# Open_Reactor_Control_System_-_Analogue_I.net
KiCad netlist of a schematic drawn in Altium Designer
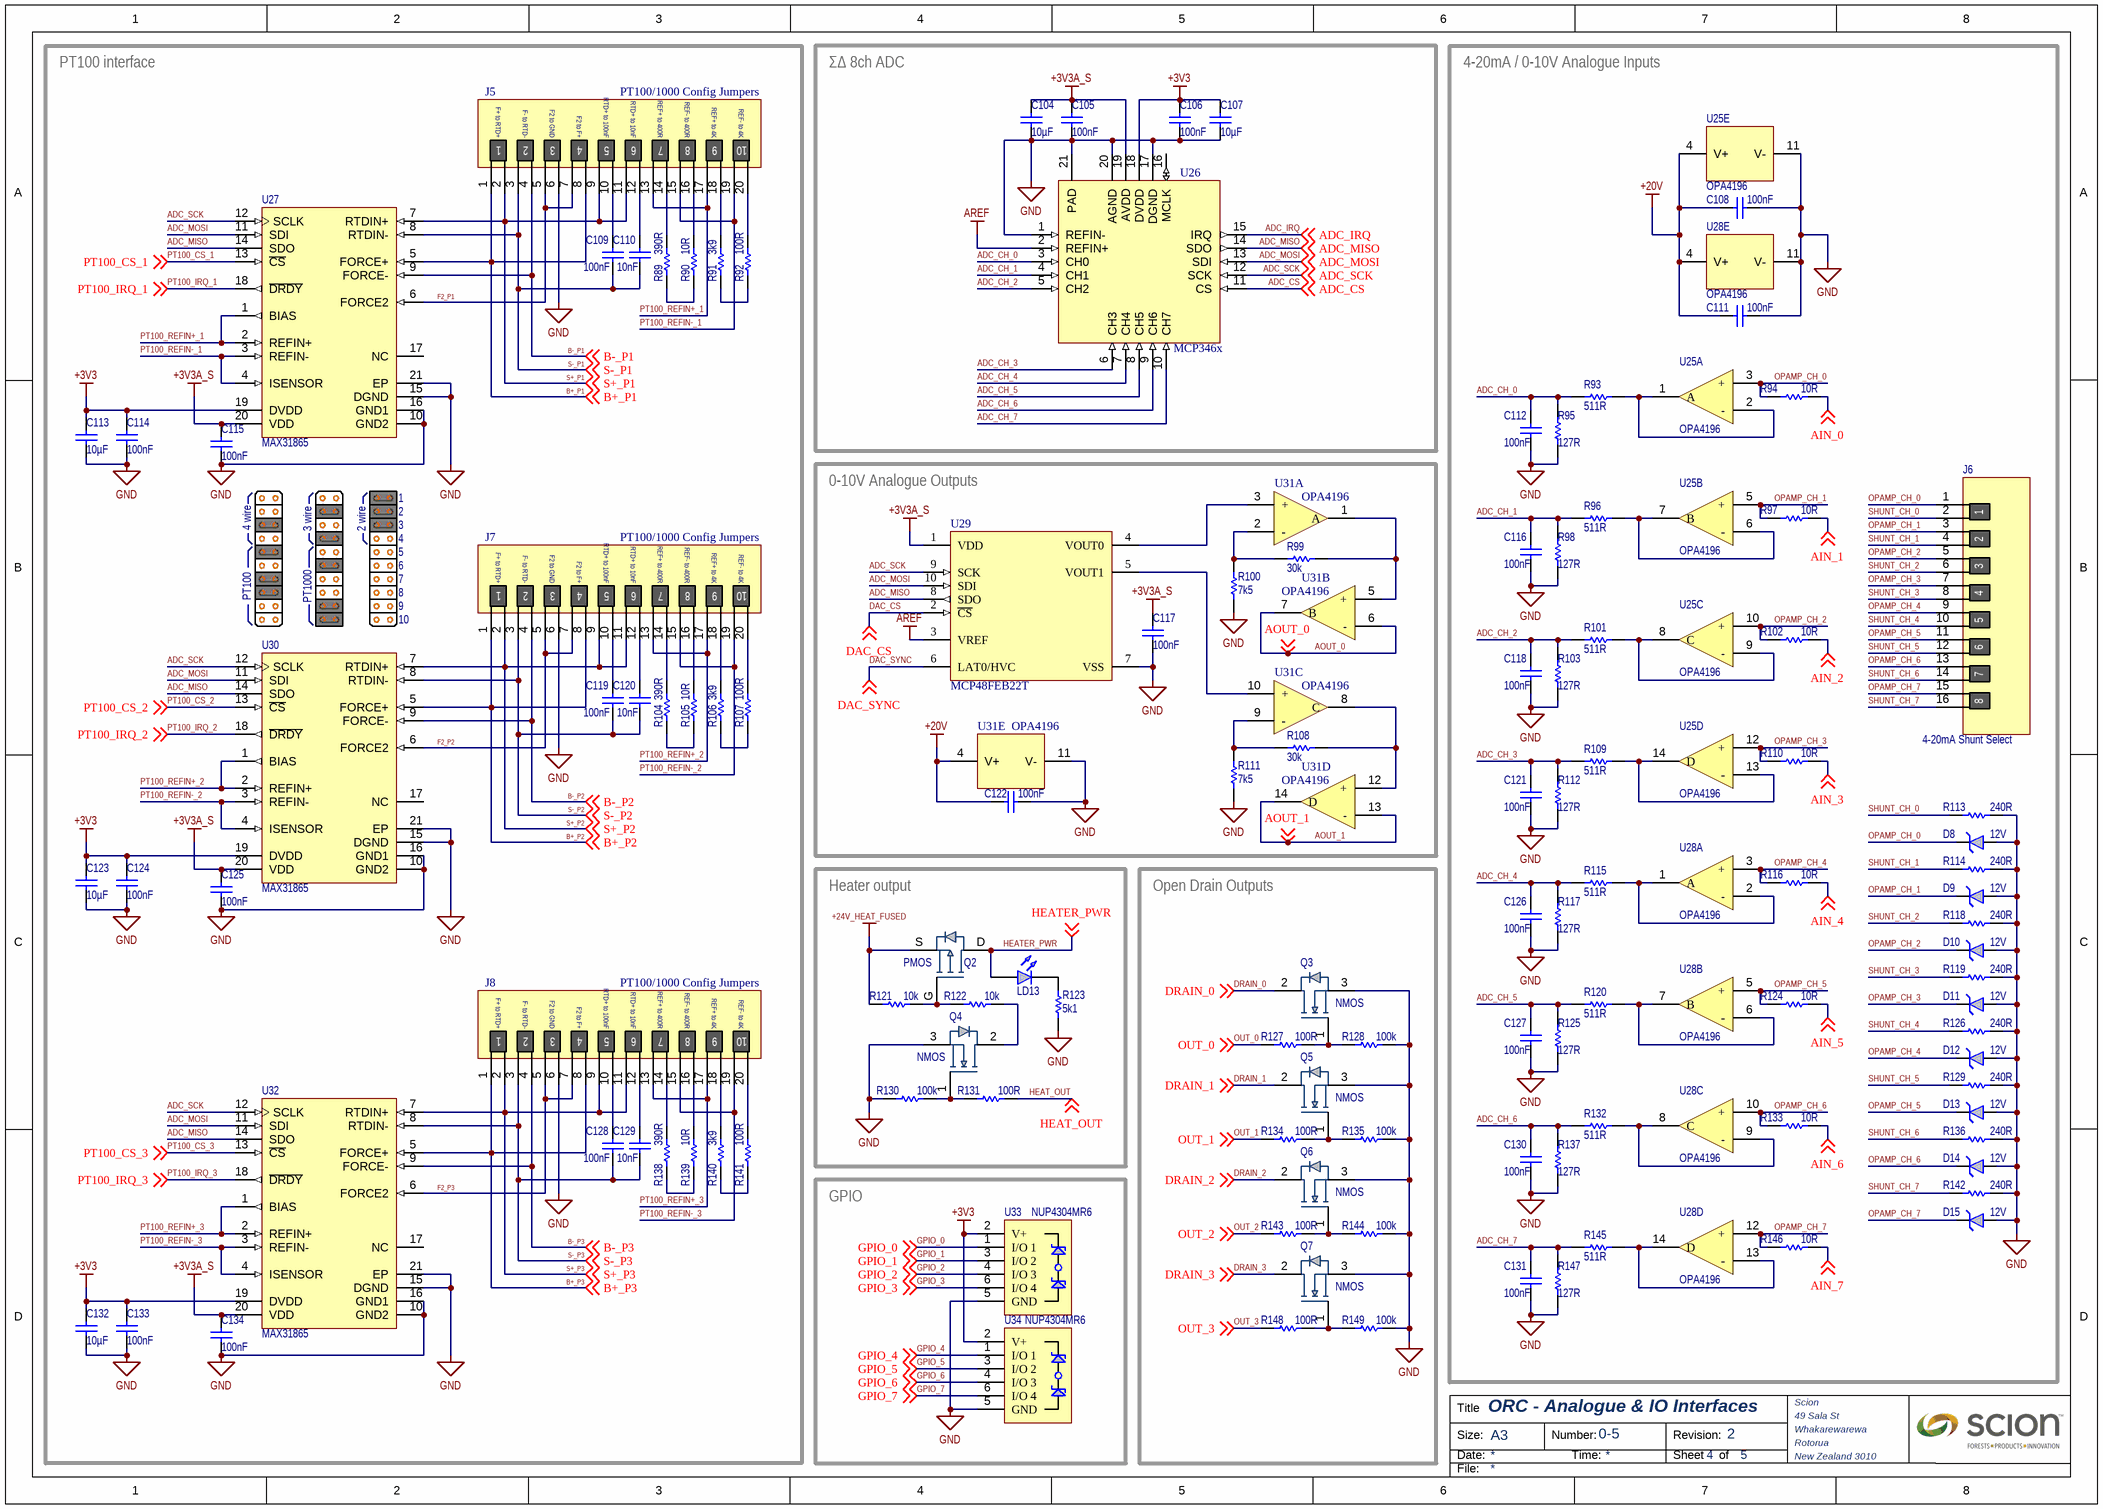
[diagram p0: Open Reactor Control System - Analogue & IO Interfaces.SchDoc]

(export (version "E")
  (design (tool "Eeschema 10.0.6"))
  (components
    (comp (ref "C104")
      (value "10µF")
      (footprint "0603_CAP")
      (description "SMD Capacitor")
      (fields (field (name "Comment") "Capacitor"))
      (libsource (lib "Scion Research") (part "CMP-019-00005-2"))
    )
    (comp (ref "C105")
      (value "100nF")
      (footprint "0603_CAP")
      (description "SMD Capacitor")
      (fields (field (name "Comment") "Capacitor"))
      (libsource (lib "Scion Research") (part "CMP-019-00005-2"))
    )
    (comp (ref "C106")
      (value "100nF")
      (footprint "0603_CAP")
      (description "SMD Capacitor")
      (fields (field (name "Comment") "Capacitor"))
      (libsource (lib "Scion Research") (part "CMP-019-00005-2"))
    )
    (comp (ref "C107")
      (value "10µF")
      (footprint "0603_CAP")
      (description "SMD Capacitor")
      (fields (field (name "Comment") "Capacitor"))
      (libsource (lib "Scion Research") (part "CMP-019-00005-2"))
    )
    (comp (ref "C108")
      (value "100nF")
      (footprint "0603_CAP")
      (description "SMD Capacitor")
      (fields (field (name "Comment") "Capacitor"))
      (libsource (lib "Scion Research") (part "CMP-019-00005-2"))
    )
    (comp (ref "C109")
      (value "100nF")
      (footprint "0603_CAP")
      (description "SMD Capacitor")
      (fields (field (name "Comment") "Capacitor"))
      (libsource (lib "Scion Research") (part "CMP-019-00005-2"))
    )
    (comp (ref "C110")
      (value "10nF")
      (footprint "0603_CAP")
      (description "SMD Capacitor")
      (fields (field (name "Comment") "Capacitor"))
      (libsource (lib "Scion Research") (part "CMP-019-00005-2"))
    )
    (comp (ref "C111")
      (value "100nF")
      (footprint "0603_CAP")
      (description "SMD Capacitor")
      (fields (field (name "Comment") "Capacitor"))
      (libsource (lib "Scion Research") (part "CMP-019-00005-2"))
    )
    (comp (ref "C112")
      (value "100nF")
      (footprint "0603_CAP")
      (description "SMD Capacitor")
      (fields (field (name "Comment") "Capacitor"))
      (libsource (lib "Scion Research") (part "CMP-019-00005-2"))
    )
    (comp (ref "C113")
      (value "10µF")
      (footprint "0603_CAP")
      (description "SMD Capacitor")
      (fields (field (name "Comment") "Capacitor"))
      (libsource (lib "Scion Research") (part "CMP-019-00005-2"))
    )
    (comp (ref "C114")
      (value "100nF")
      (footprint "0603_CAP")
      (description "SMD Capacitor")
      (fields (field (name "Comment") "Capacitor"))
      (libsource (lib "Scion Research") (part "CMP-019-00005-2"))
    )
    (comp (ref "C115")
      (value "100nF")
      (footprint "0603_CAP")
      (description "SMD Capacitor")
      (fields (field (name "Comment") "Capacitor"))
      (libsource (lib "Scion Research") (part "CMP-019-00005-2"))
    )
    (comp (ref "C116")
      (value "100nF")
      (footprint "0603_CAP")
      (description "SMD Capacitor")
      (fields (field (name "Comment") "Capacitor"))
      (libsource (lib "Scion Research") (part "CMP-019-00005-2"))
    )
    (comp (ref "C117")
      (value "100nF")
      (footprint "0603_CAP")
      (description "SMD Capacitor")
      (fields (field (name "Comment") "Capacitor"))
      (libsource (lib "Scion Research") (part "CMP-019-00005-2"))
    )
    (comp (ref "C118")
      (value "100nF")
      (footprint "0603_CAP")
      (description "SMD Capacitor")
      (fields (field (name "Comment") "Capacitor"))
      (libsource (lib "Scion Research") (part "CMP-019-00005-2"))
    )
    (comp (ref "C119")
      (value "100nF")
      (footprint "0603_CAP")
      (description "SMD Capacitor")
      (fields (field (name "Comment") "Capacitor"))
      (libsource (lib "Scion Research") (part "CMP-019-00005-2"))
    )
    (comp (ref "C120")
      (value "10nF")
      (footprint "0603_CAP")
      (description "SMD Capacitor")
      (fields (field (name "Comment") "Capacitor"))
      (libsource (lib "Scion Research") (part "CMP-019-00005-2"))
    )
    (comp (ref "C121")
      (value "100nF")
      (footprint "0603_CAP")
      (description "SMD Capacitor")
      (fields (field (name "Comment") "Capacitor"))
      (libsource (lib "Scion Research") (part "CMP-019-00005-2"))
    )
    (comp (ref "C122")
      (value "100nF")
      (footprint "0603_CAP")
      (description "SMD Capacitor")
      (fields (field (name "Comment") "Capacitor"))
      (libsource (lib "Scion Research") (part "CMP-019-00005-2"))
    )
    (comp (ref "C123")
      (value "10µF")
      (footprint "0603_CAP")
      (description "SMD Capacitor")
      (fields (field (name "Comment") "Capacitor"))
      (libsource (lib "Scion Research") (part "CMP-019-00005-2"))
    )
    (comp (ref "C124")
      (value "100nF")
      (footprint "0603_CAP")
      (description "SMD Capacitor")
      (fields (field (name "Comment") "Capacitor"))
      (libsource (lib "Scion Research") (part "CMP-019-00005-2"))
    )
    (comp (ref "C125")
      (value "100nF")
      (footprint "0603_CAP")
      (description "SMD Capacitor")
      (fields (field (name "Comment") "Capacitor"))
      (libsource (lib "Scion Research") (part "CMP-019-00005-2"))
    )
    (comp (ref "C126")
      (value "100nF")
      (footprint "0603_CAP")
      (description "SMD Capacitor")
      (fields (field (name "Comment") "Capacitor"))
      (libsource (lib "Scion Research") (part "CMP-019-00005-2"))
    )
    (comp (ref "C127")
      (value "100nF")
      (footprint "0603_CAP")
      (description "SMD Capacitor")
      (fields (field (name "Comment") "Capacitor"))
      (libsource (lib "Scion Research") (part "CMP-019-00005-2"))
    )
    (comp (ref "C128")
      (value "100nF")
      (footprint "0603_CAP")
      (description "SMD Capacitor")
      (fields (field (name "Comment") "Capacitor"))
      (libsource (lib "Scion Research") (part "CMP-019-00005-2"))
    )
    (comp (ref "C129")
      (value "10nF")
      (footprint "0603_CAP")
      (description "SMD Capacitor")
      (fields (field (name "Comment") "Capacitor"))
      (libsource (lib "Scion Research") (part "CMP-019-00005-2"))
    )
    (comp (ref "C130")
      (value "100nF")
      (footprint "0603_CAP")
      (description "SMD Capacitor")
      (fields (field (name "Comment") "Capacitor"))
      (libsource (lib "Scion Research") (part "CMP-019-00005-2"))
    )
    (comp (ref "C131")
      (value "100nF")
      (footprint "0603_CAP")
      (description "SMD Capacitor")
      (fields (field (name "Comment") "Capacitor"))
      (libsource (lib "Scion Research") (part "CMP-019-00005-2"))
    )
    (comp (ref "C132")
      (value "10µF")
      (footprint "0603_CAP")
      (description "SMD Capacitor")
      (fields (field (name "Comment") "Capacitor"))
      (libsource (lib "Scion Research") (part "CMP-019-00005-2"))
    )
    (comp (ref "C133")
      (value "100nF")
      (footprint "0603_CAP")
      (description "SMD Capacitor")
      (fields (field (name "Comment") "Capacitor"))
      (libsource (lib "Scion Research") (part "CMP-019-00005-2"))
    )
    (comp (ref "C134")
      (value "100nF")
      (footprint "0603_CAP")
      (description "SMD Capacitor")
      (fields (field (name "Comment") "Capacitor"))
      (libsource (lib "Scion Research") (part "CMP-019-00005-2"))
    )
    (comp (ref "D8")
      (value "Transil")
      (footprint "SMBJ")
      (description "Transient Voltage Suppressor")
      (fields (field (name "RATED VOLTAGE") "12V"))
      (libsource (lib "Scion Research") (part "CMP-004-0042-1"))
    )
    (comp (ref "D9")
      (value "Transil")
      (footprint "SMBJ")
      (description "Transient Voltage Suppressor")
      (fields (field (name "RATED VOLTAGE") "12V"))
      (libsource (lib "Scion Research") (part "CMP-004-0042-1"))
    )
    (comp (ref "D10")
      (value "Transil")
      (footprint "SMBJ")
      (description "Transient Voltage Suppressor")
      (fields (field (name "RATED VOLTAGE") "12V"))
      (libsource (lib "Scion Research") (part "CMP-004-0042-1"))
    )
    (comp (ref "D11")
      (value "Transil")
      (footprint "SMBJ")
      (description "Transient Voltage Suppressor")
      (fields (field (name "RATED VOLTAGE") "12V"))
      (libsource (lib "Scion Research") (part "CMP-004-0042-1"))
    )
    (comp (ref "D12")
      (value "Transil")
      (footprint "SMBJ")
      (description "Transient Voltage Suppressor")
      (fields (field (name "RATED VOLTAGE") "12V"))
      (libsource (lib "Scion Research") (part "CMP-004-0042-1"))
    )
    (comp (ref "D13")
      (value "Transil")
      (footprint "SMBJ")
      (description "Transient Voltage Suppressor")
      (fields (field (name "RATED VOLTAGE") "12V"))
      (libsource (lib "Scion Research") (part "CMP-004-0042-1"))
    )
    (comp (ref "D14")
      (value "Transil")
      (footprint "SMBJ")
      (description "Transient Voltage Suppressor")
      (fields (field (name "RATED VOLTAGE") "12V"))
      (libsource (lib "Scion Research") (part "CMP-004-0042-1"))
    )
    (comp (ref "D15")
      (value "Transil")
      (footprint "SMBJ")
      (description "Transient Voltage Suppressor")
      (fields (field (name "RATED VOLTAGE") "12V"))
      (libsource (lib "Scion Research") (part "CMP-004-0042-1"))
    )
    (comp (ref "J5")
      (value "PT100/1000 Config Jumpers")
      (footprint "20P 1.27mm SMD DIP male header")
      (description "20 pin connector")
      (libsource (lib "Scion Research") (part "20_Pin-Symbol-1"))
    )
    (comp (ref "J6")
      (value "4-20mA Shunt Select")
      (footprint "16P 1.27mm SMD DIP male header")
      (description "16 Pin Connector")
      (libsource (lib "Scion Research") (part "16_Pin_SIL"))
    )
    (comp (ref "J7")
      (value "PT100/1000 Config Jumpers")
      (footprint "20P 1.27mm SMD DIP male header")
      (description "20 pin connector")
      (libsource (lib "Scion Research") (part "20_Pin-Symbol-1"))
    )
    (comp (ref "J8")
      (value "PT100/1000 Config Jumpers")
      (footprint "20P 1.27mm SMD DIP male header")
      (description "20 pin connector")
      (libsource (lib "Scion Research") (part "20_Pin-Symbol-1"))
    )
    (comp (ref "LD13")
      (value "LED")
      (footprint "0805")
      (description "SMD LED")
      (libsource (lib "Scion Research") (part "CMP-004-00032-1"))
    )
    (comp (ref "Q2")
      (value "PMOS")
      (footprint "PowerDI 5060-8")
      (description "P Channel MOSFET")
      (libsource (lib "Scion Research") (part "CMP-004-0035-2"))
    )
    (comp (ref "Q3")
      (value "NMOS")
      (footprint "SOT-23")
      (description "N Channel MOSFET")
      (libsource (lib "Scion Research") (part "CMP-004-0025-1"))
    )
    (comp (ref "Q4")
      (value "NMOS")
      (footprint "SOT-23")
      (description "N Channel MOSFET")
      (libsource (lib "Scion Research") (part "CMP-004-0025-1"))
    )
    (comp (ref "Q5")
      (value "NMOS")
      (footprint "SOT-23")
      (description "N Channel MOSFET")
      (libsource (lib "Scion Research") (part "CMP-004-0025-1"))
    )
    (comp (ref "Q6")
      (value "NMOS")
      (footprint "SOT-23")
      (description "N Channel MOSFET")
      (libsource (lib "Scion Research") (part "CMP-004-0025-1"))
    )
    (comp (ref "Q7")
      (value "NMOS")
      (footprint "SOT-23")
      (description "N Channel MOSFET")
      (libsource (lib "Scion Research") (part "CMP-004-0025-1"))
    )
    (comp (ref "R89")
      (value "390R")
      (footprint "0603_RES")
      (description "SMD Resistor")
      (fields (field (name "Comment") "Resistor"))
      (libsource (lib "Scion Research") (part "Resistor SMD"))
    )
    (comp (ref "R90")
      (value "10R")
      (footprint "0603_RES")
      (description "SMD Resistor")
      (fields (field (name "Comment") "Resistor"))
      (libsource (lib "Scion Research") (part "Resistor SMD"))
    )
    (comp (ref "R91")
      (value "3k9")
      (footprint "0603_RES")
      (description "SMD Resistor")
      (fields (field (name "Comment") "Resistor"))
      (libsource (lib "Scion Research") (part "Resistor SMD"))
    )
    (comp (ref "R92")
      (value "100R")
      (footprint "0603_RES")
      (description "SMD Resistor")
      (fields (field (name "Comment") "Resistor"))
      (libsource (lib "Scion Research") (part "Resistor SMD"))
    )
    (comp (ref "R93")
      (value "511R")
      (footprint "0603_RES")
      (description "SMD Resistor")
      (fields (field (name "Comment") "Resistor"))
      (libsource (lib "Scion Research") (part "Resistor SMD"))
    )
    (comp (ref "R94")
      (value "10R")
      (footprint "0603_RES")
      (description "SMD Resistor")
      (fields (field (name "Comment") "Resistor"))
      (libsource (lib "Scion Research") (part "Resistor SMD"))
    )
    (comp (ref "R95")
      (value "127R")
      (footprint "0603_RES")
      (description "SMD Resistor")
      (fields (field (name "Comment") "Resistor"))
      (libsource (lib "Scion Research") (part "Resistor SMD"))
    )
    (comp (ref "R96")
      (value "511R")
      (footprint "0603_RES")
      (description "SMD Resistor")
      (fields (field (name "Comment") "Resistor"))
      (libsource (lib "Scion Research") (part "Resistor SMD"))
    )
    (comp (ref "R97")
      (value "10R")
      (footprint "0603_RES")
      (description "SMD Resistor")
      (fields (field (name "Comment") "Resistor"))
      (libsource (lib "Scion Research") (part "Resistor SMD"))
    )
    (comp (ref "R98")
      (value "127R")
      (footprint "0603_RES")
      (description "SMD Resistor")
      (fields (field (name "Comment") "Resistor"))
      (libsource (lib "Scion Research") (part "Resistor SMD"))
    )
    (comp (ref "R99")
      (value "30k")
      (footprint "0603_RES")
      (description "SMD Resistor")
      (fields (field (name "Comment") "Resistor"))
      (libsource (lib "Scion Research") (part "Resistor SMD"))
    )
    (comp (ref "R100")
      (value "7k5")
      (footprint "0603_RES")
      (description "SMD Resistor")
      (fields (field (name "Comment") "Resistor"))
      (libsource (lib "Scion Research") (part "Resistor SMD"))
    )
    (comp (ref "R101")
      (value "511R")
      (footprint "0603_RES")
      (description "SMD Resistor")
      (fields (field (name "Comment") "Resistor"))
      (libsource (lib "Scion Research") (part "Resistor SMD"))
    )
    (comp (ref "R102")
      (value "10R")
      (footprint "0603_RES")
      (description "SMD Resistor")
      (fields (field (name "Comment") "Resistor"))
      (libsource (lib "Scion Research") (part "Resistor SMD"))
    )
    (comp (ref "R103")
      (value "127R")
      (footprint "0603_RES")
      (description "SMD Resistor")
      (fields (field (name "Comment") "Resistor"))
      (libsource (lib "Scion Research") (part "Resistor SMD"))
    )
    (comp (ref "R104")
      (value "390R")
      (footprint "0603_RES")
      (description "SMD Resistor")
      (fields (field (name "Comment") "Resistor"))
      (libsource (lib "Scion Research") (part "Resistor SMD"))
    )
    (comp (ref "R105")
      (value "10R")
      (footprint "0603_RES")
      (description "SMD Resistor")
      (fields (field (name "Comment") "Resistor"))
      (libsource (lib "Scion Research") (part "Resistor SMD"))
    )
    (comp (ref "R106")
      (value "3k9")
      (footprint "0603_RES")
      (description "SMD Resistor")
      (fields (field (name "Comment") "Resistor"))
      (libsource (lib "Scion Research") (part "Resistor SMD"))
    )
    (comp (ref "R107")
      (value "100R")
      (footprint "0603_RES")
      (description "SMD Resistor")
      (fields (field (name "Comment") "Resistor"))
      (libsource (lib "Scion Research") (part "Resistor SMD"))
    )
    (comp (ref "R108")
      (value "30k")
      (footprint "0603_RES")
      (description "SMD Resistor")
      (fields (field (name "Comment") "Resistor"))
      (libsource (lib "Scion Research") (part "Resistor SMD"))
    )
    (comp (ref "R109")
      (value "511R")
      (footprint "0603_RES")
      (description "SMD Resistor")
      (fields (field (name "Comment") "Resistor"))
      (libsource (lib "Scion Research") (part "Resistor SMD"))
    )
    (comp (ref "R110")
      (value "10R")
      (footprint "0603_RES")
      (description "SMD Resistor")
      (fields (field (name "Comment") "Resistor"))
      (libsource (lib "Scion Research") (part "Resistor SMD"))
    )
    (comp (ref "R111")
      (value "7k5")
      (footprint "0603_RES")
      (description "SMD Resistor")
      (fields (field (name "Comment") "Resistor"))
      (libsource (lib "Scion Research") (part "Resistor SMD"))
    )
    (comp (ref "R112")
      (value "127R")
      (footprint "0603_RES")
      (description "SMD Resistor")
      (fields (field (name "Comment") "Resistor"))
      (libsource (lib "Scion Research") (part "Resistor SMD"))
    )
    (comp (ref "R113")
      (value "Resistor")
      (footprint "1206_RES")
      (description "SMD Resistor")
      (fields (field (name "ALTIUM_VALUE") "240R"))
      (libsource (lib "Scion Research") (part "CMP-009-00177-2"))
    )
    (comp (ref "R114")
      (value "Resistor")
      (footprint "1206_RES")
      (description "SMD Resistor")
      (fields (field (name "ALTIUM_VALUE") "240R"))
      (libsource (lib "Scion Research") (part "CMP-009-00177-2"))
    )
    (comp (ref "R115")
      (value "511R")
      (footprint "0603_RES")
      (description "SMD Resistor")
      (fields (field (name "Comment") "Resistor"))
      (libsource (lib "Scion Research") (part "Resistor SMD"))
    )
    (comp (ref "R116")
      (value "10R")
      (footprint "0603_RES")
      (description "SMD Resistor")
      (fields (field (name "Comment") "Resistor"))
      (libsource (lib "Scion Research") (part "Resistor SMD"))
    )
    (comp (ref "R117")
      (value "127R")
      (footprint "0603_RES")
      (description "SMD Resistor")
      (fields (field (name "Comment") "Resistor"))
      (libsource (lib "Scion Research") (part "Resistor SMD"))
    )
    (comp (ref "R118")
      (value "Resistor")
      (footprint "1206_RES")
      (description "SMD Resistor")
      (fields (field (name "ALTIUM_VALUE") "240R"))
      (libsource (lib "Scion Research") (part "CMP-009-00177-2"))
    )
    (comp (ref "R119")
      (value "Resistor")
      (footprint "1206_RES")
      (description "SMD Resistor")
      (fields (field (name "ALTIUM_VALUE") "240R"))
      (libsource (lib "Scion Research") (part "CMP-009-00177-2"))
    )
    (comp (ref "R120")
      (value "511R")
      (footprint "0603_RES")
      (description "SMD Resistor")
      (fields (field (name "Comment") "Resistor"))
      (libsource (lib "Scion Research") (part "Resistor SMD"))
    )
    (comp (ref "R121")
      (value "10k")
      (footprint "0603_RES")
      (description "SMD Resistor")
      (fields (field (name "Comment") "Resistor"))
      (libsource (lib "Scion Research") (part "Resistor SMD"))
    )
    (comp (ref "R122")
      (value "10k")
      (footprint "0603_RES")
      (description "SMD Resistor")
      (fields (field (name "Comment") "Resistor"))
      (libsource (lib "Scion Research") (part "Resistor SMD"))
    )
    (comp (ref "R123")
      (value "Resistor")
      (footprint "0603_RES")
      (description "SMD Resistor")
      (fields (field (name "ALTIUM_VALUE") "5k1"))
      (libsource (lib "Scion Research") (part "CMP-009-00177-2"))
    )
    (comp (ref "R124")
      (value "10R")
      (footprint "0603_RES")
      (description "SMD Resistor")
      (fields (field (name "Comment") "Resistor"))
      (libsource (lib "Scion Research") (part "Resistor SMD"))
    )
    (comp (ref "R125")
      (value "127R")
      (footprint "0603_RES")
      (description "SMD Resistor")
      (fields (field (name "Comment") "Resistor"))
      (libsource (lib "Scion Research") (part "Resistor SMD"))
    )
    (comp (ref "R126")
      (value "Resistor")
      (footprint "1206_RES")
      (description "SMD Resistor")
      (fields (field (name "ALTIUM_VALUE") "240R"))
      (libsource (lib "Scion Research") (part "CMP-009-00177-2"))
    )
    (comp (ref "R127")
      (value "100R")
      (footprint "0603_RES")
      (description "SMD Resistor")
      (fields (field (name "Comment") "Resistor"))
      (libsource (lib "Scion Research") (part "Resistor SMD"))
    )
    (comp (ref "R128")
      (value "100k")
      (footprint "0603_RES")
      (description "SMD Resistor")
      (fields (field (name "Comment") "Resistor"))
      (libsource (lib "Scion Research") (part "Resistor SMD"))
    )
    (comp (ref "R129")
      (value "Resistor")
      (footprint "1206_RES")
      (description "SMD Resistor")
      (fields (field (name "ALTIUM_VALUE") "240R"))
      (libsource (lib "Scion Research") (part "CMP-009-00177-2"))
    )
    (comp (ref "R130")
      (value "100k")
      (footprint "0603_RES")
      (description "SMD Resistor")
      (fields (field (name "Comment") "Resistor"))
      (libsource (lib "Scion Research") (part "Resistor SMD"))
    )
    (comp (ref "R131")
      (value "100R")
      (footprint "0603_RES")
      (description "SMD Resistor")
      (fields (field (name "Comment") "Resistor"))
      (libsource (lib "Scion Research") (part "Resistor SMD"))
    )
    (comp (ref "R132")
      (value "511R")
      (footprint "0603_RES")
      (description "SMD Resistor")
      (fields (field (name "Comment") "Resistor"))
      (libsource (lib "Scion Research") (part "Resistor SMD"))
    )
    (comp (ref "R133")
      (value "10R")
      (footprint "0603_RES")
      (description "SMD Resistor")
      (fields (field (name "Comment") "Resistor"))
      (libsource (lib "Scion Research") (part "Resistor SMD"))
    )
    (comp (ref "R134")
      (value "100R")
      (footprint "0603_RES")
      (description "SMD Resistor")
      (fields (field (name "Comment") "Resistor"))
      (libsource (lib "Scion Research") (part "Resistor SMD"))
    )
    (comp (ref "R135")
      (value "100k")
      (footprint "0603_RES")
      (description "SMD Resistor")
      (fields (field (name "Comment") "Resistor"))
      (libsource (lib "Scion Research") (part "Resistor SMD"))
    )
    (comp (ref "R136")
      (value "Resistor")
      (footprint "1206_RES")
      (description "SMD Resistor")
      (fields (field (name "ALTIUM_VALUE") "240R"))
      (libsource (lib "Scion Research") (part "CMP-009-00177-2"))
    )
    (comp (ref "R137")
      (value "127R")
      (footprint "0603_RES")
      (description "SMD Resistor")
      (fields (field (name "Comment") "Resistor"))
      (libsource (lib "Scion Research") (part "Resistor SMD"))
    )
    (comp (ref "R138")
      (value "390R")
      (footprint "0603_RES")
      (description "SMD Resistor")
      (fields (field (name "Comment") "Resistor"))
      (libsource (lib "Scion Research") (part "Resistor SMD"))
    )
    (comp (ref "R139")
      (value "10R")
      (footprint "0603_RES")
      (description "SMD Resistor")
      (fields (field (name "Comment") "Resistor"))
      (libsource (lib "Scion Research") (part "Resistor SMD"))
    )
    (comp (ref "R140")
      (value "3k9")
      (footprint "0603_RES")
      (description "SMD Resistor")
      (fields (field (name "Comment") "Resistor"))
      (libsource (lib "Scion Research") (part "Resistor SMD"))
    )
    (comp (ref "R141")
      (value "100R")
      (footprint "0603_RES")
      (description "SMD Resistor")
      (fields (field (name "Comment") "Resistor"))
      (libsource (lib "Scion Research") (part "Resistor SMD"))
    )
    (comp (ref "R142")
      (value "Resistor")
      (footprint "1206_RES")
      (description "SMD Resistor")
      (fields (field (name "ALTIUM_VALUE") "240R"))
      (libsource (lib "Scion Research") (part "CMP-009-00177-2"))
    )
    (comp (ref "R143")
      (value "100R")
      (footprint "0603_RES")
      (description "SMD Resistor")
      (fields (field (name "Comment") "Resistor"))
      (libsource (lib "Scion Research") (part "Resistor SMD"))
    )
    (comp (ref "R144")
      (value "100k")
      (footprint "0603_RES")
      (description "SMD Resistor")
      (fields (field (name "Comment") "Resistor"))
      (libsource (lib "Scion Research") (part "Resistor SMD"))
    )
    (comp (ref "R145")
      (value "511R")
      (footprint "0603_RES")
      (description "SMD Resistor")
      (fields (field (name "Comment") "Resistor"))
      (libsource (lib "Scion Research") (part "Resistor SMD"))
    )
    (comp (ref "R146")
      (value "10R")
      (footprint "0603_RES")
      (description "SMD Resistor")
      (fields (field (name "Comment") "Resistor"))
      (libsource (lib "Scion Research") (part "Resistor SMD"))
    )
    (comp (ref "R147")
      (value "127R")
      (footprint "0603_RES")
      (description "SMD Resistor")
      (fields (field (name "Comment") "Resistor"))
      (libsource (lib "Scion Research") (part "Resistor SMD"))
    )
    (comp (ref "R148")
      (value "100R")
      (footprint "0603_RES")
      (description "SMD Resistor")
      (fields (field (name "Comment") "Resistor"))
      (libsource (lib "Scion Research") (part "Resistor SMD"))
    )
    (comp (ref "R149")
      (value "100k")
      (footprint "0603_RES")
      (description "SMD Resistor")
      (fields (field (name "Comment") "Resistor"))
      (libsource (lib "Scion Research") (part "Resistor SMD"))
    )
    (comp (ref "U25")
      (value "OPA4196")
      (footprint "SOIC_14")
      (description "Quad 36V OpAmp")
      (libsource (lib "") (part "CMP-004-0029-1_1"))
    )
    (comp (ref "U26")
      (value "MCP346x")
      (footprint "20P_TSSOP")
      (description "MCP3461/2/4 S? ADC")
      (libsource (lib "Scion Research") (part "MCP3464"))
    )
    (comp (ref "U27")
      (value "MAX31865")
      (footprint "MAXM-T2055+5_L")
      (description "IC RTD TO DIGITAL CONVERT 20TQFN")
      (libsource (lib "Scion Research") (part "CMP-00054-1"))
    )
    (comp (ref "U28")
      (value "OPA4196")
      (footprint "SOIC_14")
      (description "Quad 36V OpAmp")
      (libsource (lib "Scion Research") (part "CMP-004-0029-1"))
    )
    (comp (ref "U29")
      (value "MCP48FEB22T")
      (footprint "FP-C04-021-UN-IPC_C")
      (description "D/A Converter, 1 Func, Serial Input Loading, 7.8us Settling Time, PDSO10")
      (libsource (lib "Scion Research") (part "MCP48FEB22"))
    )
    (comp (ref "U30")
      (value "MAX31865")
      (footprint "MAXM-T2055+5_L")
      (description "IC RTD TO DIGITAL CONVERT 20TQFN")
      (libsource (lib "Scion Research") (part "CMP-00054-1"))
    )
    (comp (ref "U31")
      (value "OPA4196")
      (footprint "SOIC_14")
      (description "Quad 36V OpAmp")
      (libsource (lib "") (part "CMP-004-0029-1_1"))
    )
    (comp (ref "U32")
      (value "MAX31865")
      (footprint "MAXM-T2055+5_L")
      (description "IC RTD TO DIGITAL CONVERT 20TQFN")
      (libsource (lib "Scion Research") (part "CMP-00054-1"))
    )
    (comp (ref "U33")
      (value "NUP4304MR6")
      (footprint "TSOP-6")
      (description "ESD Protection Doide Array")
      (libsource (lib "Scion Research") (part "CMP-004-0028-1"))
    )
    (comp (ref "U34")
      (value "NUP4304MR6")
      (footprint "TSOP-6")
      (description "ESD Protection Doide Array")
      (libsource (lib "Scion Research") (part "CMP-004-0028-1"))
    )
  )
  (nets
    (net (code "1") (name "+3V3") (class "Default")
      (node (ref "C106") (pin "1") (pinfunction "1_1") (pintype "passive"))
      (node (ref "C107") (pin "1") (pinfunction "1_1") (pintype "passive"))
      (node (ref "C113") (pin "1") (pinfunction "1_1") (pintype "passive"))
      (node (ref "C114") (pin "1") (pinfunction "1_1") (pintype "passive"))
      (node (ref "C123") (pin "1") (pinfunction "1_1") (pintype "passive"))
      (node (ref "C124") (pin "1") (pinfunction "1_1") (pintype "passive"))
      (node (ref "C132") (pin "1") (pinfunction "1_1") (pintype "passive"))
      (node (ref "C133") (pin "1") (pinfunction "1_1") (pintype "passive"))
      (node (ref "U26") (pin "18") (pinfunction "DVDD_18") (pintype "power_in"))
      (node (ref "U27") (pin "19") (pinfunction "DVDD_19") (pintype "power_in"))
      (node (ref "U30") (pin "19") (pinfunction "DVDD_19") (pintype "power_in"))
      (node (ref "U32") (pin "19") (pinfunction "DVDD_19") (pintype "power_in"))
      (node (ref "U33") (pin "2") (pinfunction "V+_2") (pintype "power_in"))
      (node (ref "U34") (pin "2") (pinfunction "V+_2") (pintype "power_in"))
    )
    (net (code "2") (name "+3V3A_S") (class "Default")
      (node (ref "C104") (pin "1") (pinfunction "1_1") (pintype "passive"))
      (node (ref "C105") (pin "1") (pinfunction "1_1") (pintype "passive"))
      (node (ref "C115") (pin "1") (pinfunction "1_1") (pintype "passive"))
      (node (ref "C117") (pin "1") (pinfunction "1_1") (pintype "passive"))
      (node (ref "C125") (pin "1") (pinfunction "1_1") (pintype "passive"))
      (node (ref "C134") (pin "1") (pinfunction "1_1") (pintype "passive"))
      (node (ref "U26") (pin "19") (pinfunction "AVDD_19") (pintype "power_in"))
      (node (ref "U27") (pin "20") (pinfunction "VDD_20") (pintype "power_in"))
      (node (ref "U29") (pin "1") (pinfunction "VDD_1") (pintype "power_in"))
      (node (ref "U30") (pin "20") (pinfunction "VDD_20") (pintype "power_in"))
      (node (ref "U32") (pin "20") (pinfunction "VDD_20") (pintype "power_in"))
    )
    (net (code "3") (name "+20V") (class "Default")
      (node (ref "C108") (pin "1") (pinfunction "1_1") (pintype "passive"))
      (node (ref "C111") (pin "1") (pinfunction "1_1") (pintype "passive"))
      (node (ref "C122") (pin "2") (pinfunction "2_2") (pintype "passive"))
      (node (ref "U25") (pin "4") (pinfunction "V+_4") (pintype "passive"))
      (node (ref "U28") (pin "4") (pinfunction "V+_4") (pintype "passive"))
      (node (ref "U31") (pin "4") (pinfunction "V+_4") (pintype "passive"))
    )
    (net (code "4") (name "+24V_HEAT_FUSED") (class "Default")
      (node (ref "Q2") (pin "S") (pinfunction "S_S") (pintype "passive"))
      (node (ref "R121") (pin "2") (pinfunction "2_2") (pintype "passive"))
    )
    (net (code "5") (name "/ADC_CH_0") (class "Default")
      (node (ref "C112") (pin "1") (pinfunction "1_1") (pintype "passive"))
      (node (ref "R93") (pin "2") (pinfunction "2_2") (pintype "passive"))
      (node (ref "R95") (pin "2") (pinfunction "2_2") (pintype "passive"))
      (node (ref "U26") (pin "3") (pinfunction "CH0_3") (pintype "input"))
    )
    (net (code "6") (name "/ADC_CH_1") (class "Default")
      (node (ref "C116") (pin "1") (pinfunction "1_1") (pintype "passive"))
      (node (ref "R96") (pin "2") (pinfunction "2_2") (pintype "passive"))
      (node (ref "R98") (pin "2") (pinfunction "2_2") (pintype "passive"))
      (node (ref "U26") (pin "4") (pinfunction "CH1_4") (pintype "input"))
    )
    (net (code "7") (name "/ADC_CH_2") (class "Default")
      (node (ref "C118") (pin "1") (pinfunction "1_1") (pintype "passive"))
      (node (ref "R101") (pin "2") (pinfunction "2_2") (pintype "passive"))
      (node (ref "R103") (pin "2") (pinfunction "2_2") (pintype "passive"))
      (node (ref "U26") (pin "5") (pinfunction "CH2_5") (pintype "input"))
    )
    (net (code "8") (name "/ADC_CH_3") (class "Default")
      (node (ref "C121") (pin "1") (pinfunction "1_1") (pintype "passive"))
      (node (ref "R109") (pin "2") (pinfunction "2_2") (pintype "passive"))
      (node (ref "R112") (pin "2") (pinfunction "2_2") (pintype "passive"))
      (node (ref "U26") (pin "6") (pinfunction "CH3_6") (pintype "input"))
    )
    (net (code "9") (name "/ADC_CH_4") (class "Default")
      (node (ref "C126") (pin "1") (pinfunction "1_1") (pintype "passive"))
      (node (ref "R115") (pin "2") (pinfunction "2_2") (pintype "passive"))
      (node (ref "R117") (pin "2") (pinfunction "2_2") (pintype "passive"))
      (node (ref "U26") (pin "7") (pinfunction "CH4_7") (pintype "input"))
    )
    (net (code "10") (name "/ADC_CH_5") (class "Default")
      (node (ref "C127") (pin "1") (pinfunction "1_1") (pintype "passive"))
      (node (ref "R120") (pin "2") (pinfunction "2_2") (pintype "passive"))
      (node (ref "R125") (pin "2") (pinfunction "2_2") (pintype "passive"))
      (node (ref "U26") (pin "8") (pinfunction "CH5_8") (pintype "input"))
    )
    (net (code "11") (name "/ADC_CH_6") (class "Default")
      (node (ref "C130") (pin "1") (pinfunction "1_1") (pintype "passive"))
      (node (ref "R132") (pin "2") (pinfunction "2_2") (pintype "passive"))
      (node (ref "R137") (pin "2") (pinfunction "2_2") (pintype "passive"))
      (node (ref "U26") (pin "9") (pinfunction "CH6_9") (pintype "input"))
    )
    (net (code "12") (name "/ADC_CH_7") (class "Default")
      (node (ref "C131") (pin "1") (pinfunction "1_1") (pintype "passive"))
      (node (ref "R145") (pin "2") (pinfunction "2_2") (pintype "passive"))
      (node (ref "R147") (pin "2") (pinfunction "2_2") (pintype "passive"))
      (node (ref "U26") (pin "10") (pinfunction "CH7_10") (pintype "input"))
    )
    (net (code "13") (name "/F2_P1") (class "Default")
      (node (ref "J5") (pin "5") (pinfunction "5_5") (pintype "passive"))
      (node (ref "J5") (pin "7") (pinfunction "7_7") (pintype "passive"))
      (node (ref "U27") (pin "6") (pinfunction "FORCE2_6") (pintype "input"))
    )
    (net (code "14") (name "/F2_P2") (class "Default")
      (node (ref "J7") (pin "5") (pinfunction "5_5") (pintype "passive"))
      (node (ref "J7") (pin "7") (pinfunction "7_7") (pintype "passive"))
      (node (ref "U30") (pin "6") (pinfunction "FORCE2_6") (pintype "input"))
    )
    (net (code "15") (name "/F2_P3") (class "Default")
      (node (ref "J8") (pin "5") (pinfunction "5_5") (pintype "passive"))
      (node (ref "J8") (pin "7") (pinfunction "7_7") (pintype "passive"))
      (node (ref "U32") (pin "6") (pinfunction "FORCE2_6") (pintype "input"))
    )
    (net (code "16") (name "/OPAMP_CH_0") (class "Default")
      (node (ref "D8") (pin "2") (pinfunction "K_2") (pintype "passive"))
      (node (ref "J6") (pin "1") (pinfunction "1_1") (pintype "passive"))
      (node (ref "R94") (pin "2") (pinfunction "2_2") (pintype "passive"))
      (node (ref "U25") (pin "3") (pinfunction "+_3") (pintype "passive"))
    )
    (net (code "17") (name "/OPAMP_CH_1") (class "Default")
      (node (ref "D9") (pin "2") (pinfunction "K_2") (pintype "passive"))
      (node (ref "J6") (pin "3") (pinfunction "3_3") (pintype "passive"))
      (node (ref "R97") (pin "2") (pinfunction "2_2") (pintype "passive"))
      (node (ref "U25") (pin "5") (pinfunction "+_5") (pintype "passive"))
    )
    (net (code "18") (name "/OPAMP_CH_2") (class "Default")
      (node (ref "D10") (pin "2") (pinfunction "K_2") (pintype "passive"))
      (node (ref "J6") (pin "5") (pinfunction "5_5") (pintype "passive"))
      (node (ref "R102") (pin "2") (pinfunction "2_2") (pintype "passive"))
      (node (ref "U25") (pin "10") (pinfunction "+_10") (pintype "passive"))
    )
    (net (code "19") (name "/OPAMP_CH_3") (class "Default")
      (node (ref "D11") (pin "2") (pinfunction "K_2") (pintype "passive"))
      (node (ref "J6") (pin "7") (pinfunction "7_7") (pintype "passive"))
      (node (ref "R110") (pin "2") (pinfunction "2_2") (pintype "passive"))
      (node (ref "U25") (pin "12") (pinfunction "+_12") (pintype "passive"))
    )
    (net (code "20") (name "/OPAMP_CH_4") (class "Default")
      (node (ref "D12") (pin "2") (pinfunction "K_2") (pintype "passive"))
      (node (ref "J6") (pin "9") (pinfunction "9_9") (pintype "passive"))
      (node (ref "R116") (pin "2") (pinfunction "2_2") (pintype "passive"))
      (node (ref "U28") (pin "3") (pinfunction "+_3") (pintype "passive"))
    )
    (net (code "21") (name "/OPAMP_CH_5") (class "Default")
      (node (ref "D13") (pin "2") (pinfunction "K_2") (pintype "passive"))
      (node (ref "J6") (pin "11") (pinfunction "11_11") (pintype "passive"))
      (node (ref "R124") (pin "2") (pinfunction "2_2") (pintype "passive"))
      (node (ref "U28") (pin "5") (pinfunction "+_5") (pintype "passive"))
    )
    (net (code "22") (name "/OPAMP_CH_6") (class "Default")
      (node (ref "D14") (pin "2") (pinfunction "K_2") (pintype "passive"))
      (node (ref "J6") (pin "13") (pinfunction "13_13") (pintype "passive"))
      (node (ref "R133") (pin "2") (pinfunction "2_2") (pintype "passive"))
      (node (ref "U28") (pin "10") (pinfunction "+_10") (pintype "passive"))
    )
    (net (code "23") (name "/OPAMP_CH_7") (class "Default")
      (node (ref "D15") (pin "2") (pinfunction "K_2") (pintype "passive"))
      (node (ref "J6") (pin "15") (pinfunction "15_15") (pintype "passive"))
      (node (ref "R146") (pin "2") (pinfunction "2_2") (pintype "passive"))
      (node (ref "U28") (pin "12") (pinfunction "+_12") (pintype "passive"))
    )
    (net (code "24") (name "/PT100_REFIN+_1") (class "Default")
      (node (ref "J5") (pin "13") (pinfunction "13_13") (pintype "passive"))
      (node (ref "J5") (pin "17") (pinfunction "17_17") (pintype "passive"))
      (node (ref "U27") (pin "1") (pinfunction "BIAS_1") (pintype "output"))
      (node (ref "U27") (pin "2") (pinfunction "REFIN+_2") (pintype "input"))
    )
    (net (code "25") (name "/PT100_REFIN+_2") (class "Default")
      (node (ref "J7") (pin "13") (pinfunction "13_13") (pintype "passive"))
      (node (ref "J7") (pin "17") (pinfunction "17_17") (pintype "passive"))
      (node (ref "U30") (pin "1") (pinfunction "BIAS_1") (pintype "output"))
      (node (ref "U30") (pin "2") (pinfunction "REFIN+_2") (pintype "input"))
    )
    (net (code "26") (name "/PT100_REFIN+_3") (class "Default")
      (node (ref "J8") (pin "13") (pinfunction "13_13") (pintype "passive"))
      (node (ref "J8") (pin "17") (pinfunction "17_17") (pintype "passive"))
      (node (ref "U32") (pin "1") (pinfunction "BIAS_1") (pintype "output"))
      (node (ref "U32") (pin "2") (pinfunction "REFIN+_2") (pintype "input"))
    )
    (net (code "27") (name "/PT100_REFIN-_1") (class "Default")
      (node (ref "J5") (pin "15") (pinfunction "15_15") (pintype "passive"))
      (node (ref "J5") (pin "19") (pinfunction "19_19") (pintype "passive"))
      (node (ref "U27") (pin "3") (pinfunction "REFIN-_3") (pintype "input"))
      (node (ref "U27") (pin "4") (pinfunction "ISENSOR_4") (pintype "input"))
    )
    (net (code "28") (name "/PT100_REFIN-_2") (class "Default")
      (node (ref "J7") (pin "15") (pinfunction "15_15") (pintype "passive"))
      (node (ref "J7") (pin "19") (pinfunction "19_19") (pintype "passive"))
      (node (ref "U30") (pin "3") (pinfunction "REFIN-_3") (pintype "input"))
      (node (ref "U30") (pin "4") (pinfunction "ISENSOR_4") (pintype "input"))
    )
    (net (code "29") (name "/PT100_REFIN-_3") (class "Default")
      (node (ref "J8") (pin "15") (pinfunction "15_15") (pintype "passive"))
      (node (ref "J8") (pin "19") (pinfunction "19_19") (pintype "passive"))
      (node (ref "U32") (pin "3") (pinfunction "REFIN-_3") (pintype "input"))
      (node (ref "U32") (pin "4") (pinfunction "ISENSOR_4") (pintype "input"))
    )
    (net (code "30") (name "/SHUNT_CH_0") (class "Default")
      (node (ref "J6") (pin "2") (pinfunction "2_2") (pintype "passive"))
      (node (ref "R113") (pin "2") (pinfunction "2_2") (pintype "passive"))
    )
    (net (code "31") (name "/SHUNT_CH_1") (class "Default")
      (node (ref "J6") (pin "4") (pinfunction "4_4") (pintype "passive"))
      (node (ref "R114") (pin "2") (pinfunction "2_2") (pintype "passive"))
    )
    (net (code "32") (name "/SHUNT_CH_2") (class "Default")
      (node (ref "J6") (pin "6") (pinfunction "6_6") (pintype "passive"))
      (node (ref "R118") (pin "2") (pinfunction "2_2") (pintype "passive"))
    )
    (net (code "33") (name "/SHUNT_CH_3") (class "Default")
      (node (ref "J6") (pin "8") (pinfunction "8_8") (pintype "passive"))
      (node (ref "R119") (pin "2") (pinfunction "2_2") (pintype "passive"))
    )
    (net (code "34") (name "/SHUNT_CH_4") (class "Default")
      (node (ref "J6") (pin "10") (pinfunction "10_10") (pintype "passive"))
      (node (ref "R126") (pin "2") (pinfunction "2_2") (pintype "passive"))
    )
    (net (code "35") (name "/SHUNT_CH_5") (class "Default")
      (node (ref "J6") (pin "12") (pinfunction "12_12") (pintype "passive"))
      (node (ref "R129") (pin "2") (pinfunction "2_2") (pintype "passive"))
    )
    (net (code "36") (name "/SHUNT_CH_6") (class "Default")
      (node (ref "J6") (pin "14") (pinfunction "14_14") (pintype "passive"))
      (node (ref "R136") (pin "2") (pinfunction "2_2") (pintype "passive"))
    )
    (net (code "37") (name "/SHUNT_CH_7") (class "Default")
      (node (ref "J6") (pin "16") (pinfunction "16_16") (pintype "passive"))
      (node (ref "R142") (pin "2") (pinfunction "2_2") (pintype "passive"))
    )
    (net (code "38") (name "ADC_CS") (class "Default")
      (node (ref "U26") (pin "11") (pinfunction "CS_11") (pintype "input"))
    )
    (net (code "39") (name "ADC_IRQ") (class "Default")
      (node (ref "U26") (pin "15") (pinfunction "IRQ_15") (pintype "output"))
    )
    (net (code "40") (name "ADC_MISO") (class "Default")
      (node (ref "U26") (pin "14") (pinfunction "SDO_14") (pintype "output"))
      (node (ref "U27") (pin "14") (pinfunction "SDO_14") (pintype "tri_state"))
      (node (ref "U29") (pin "8") (pinfunction "SDO_8") (pintype "output"))
      (node (ref "U30") (pin "14") (pinfunction "SDO_14") (pintype "tri_state"))
      (node (ref "U32") (pin "14") (pinfunction "SDO_14") (pintype "tri_state"))
    )
    (net (code "41") (name "ADC_MOSI") (class "Default")
      (node (ref "U26") (pin "13") (pinfunction "SDI_13") (pintype "input"))
      (node (ref "U27") (pin "11") (pinfunction "SDI_11") (pintype "input"))
      (node (ref "U29") (pin "10") (pinfunction "SDI_10") (pintype "input"))
      (node (ref "U30") (pin "11") (pinfunction "SDI_11") (pintype "input"))
      (node (ref "U32") (pin "11") (pinfunction "SDI_11") (pintype "input"))
    )
    (net (code "42") (name "ADC_SCK") (class "Default")
      (node (ref "U26") (pin "12") (pinfunction "SCK_12") (pintype "input"))
      (node (ref "U27") (pin "12") (pinfunction "SCLK_12") (pintype "input"))
      (node (ref "U29") (pin "9") (pinfunction "SCK_9") (pintype "input"))
      (node (ref "U30") (pin "12") (pinfunction "SCLK_12") (pintype "input"))
      (node (ref "U32") (pin "12") (pinfunction "SCLK_12") (pintype "input"))
    )
    (net (code "43") (name "AIN_0") (class "Default")
      (node (ref "R94") (pin "1") (pinfunction "1_1") (pintype "passive"))
    )
    (net (code "44") (name "AIN_1") (class "Default")
      (node (ref "R97") (pin "1") (pinfunction "1_1") (pintype "passive"))
    )
    (net (code "45") (name "AIN_2") (class "Default")
      (node (ref "R102") (pin "1") (pinfunction "1_1") (pintype "passive"))
    )
    (net (code "46") (name "AIN_3") (class "Default")
      (node (ref "R110") (pin "1") (pinfunction "1_1") (pintype "passive"))
    )
    (net (code "47") (name "AIN_4") (class "Default")
      (node (ref "R116") (pin "1") (pinfunction "1_1") (pintype "passive"))
    )
    (net (code "48") (name "AIN_5") (class "Default")
      (node (ref "R124") (pin "1") (pinfunction "1_1") (pintype "passive"))
    )
    (net (code "49") (name "AIN_6") (class "Default")
      (node (ref "R133") (pin "1") (pinfunction "1_1") (pintype "passive"))
    )
    (net (code "50") (name "AIN_7") (class "Default")
      (node (ref "R146") (pin "1") (pinfunction "1_1") (pintype "passive"))
    )
    (net (code "51") (name "AOUT_0") (class "Default")
      (node (ref "U31") (pin "6") (pinfunction "-_6") (pintype "passive"))
      (node (ref "U31") (pin "7") (pinfunction "B_7") (pintype "passive"))
    )
    (net (code "52") (name "AOUT_1") (class "Default")
      (node (ref "U31") (pin "13") (pinfunction "-_13") (pintype "passive"))
      (node (ref "U31") (pin "14") (pinfunction "D_14") (pintype "passive"))
    )
    (net (code "53") (name "AREF") (class "Default")
      (node (ref "U26") (pin "2") (pinfunction "REFIN+_2") (pintype "input"))
      (node (ref "U29") (pin "3") (pinfunction "VREF_3") (pintype "passive"))
    )
    (net (code "54") (name "B+_P1") (class "Default")
      (node (ref "J5") (pin "1") (pinfunction "1_1") (pintype "passive"))
      (node (ref "J5") (pin "8") (pinfunction "8_8") (pintype "passive"))
      (node (ref "U27") (pin "5") (pinfunction "FORCE+_5") (pintype "input"))
    )
    (net (code "55") (name "B+_P2") (class "Default")
      (node (ref "J7") (pin "1") (pinfunction "1_1") (pintype "passive"))
      (node (ref "J7") (pin "8") (pinfunction "8_8") (pintype "passive"))
      (node (ref "U30") (pin "5") (pinfunction "FORCE+_5") (pintype "input"))
    )
    (net (code "56") (name "B+_P3") (class "Default")
      (node (ref "J8") (pin "1") (pinfunction "1_1") (pintype "passive"))
      (node (ref "J8") (pin "8") (pinfunction "8_8") (pintype "passive"))
      (node (ref "U32") (pin "5") (pinfunction "FORCE+_5") (pintype "input"))
    )
    (net (code "57") (name "B-_P1") (class "Default")
      (node (ref "J5") (pin "4") (pinfunction "4_4") (pintype "passive"))
      (node (ref "U27") (pin "9") (pinfunction "FORCE-_9") (pintype "input"))
    )
    (net (code "58") (name "B-_P2") (class "Default")
      (node (ref "J7") (pin "4") (pinfunction "4_4") (pintype "passive"))
      (node (ref "U30") (pin "9") (pinfunction "FORCE-_9") (pintype "input"))
    )
    (net (code "59") (name "B-_P3") (class "Default")
      (node (ref "J8") (pin "4") (pinfunction "4_4") (pintype "passive"))
      (node (ref "U32") (pin "9") (pinfunction "FORCE-_9") (pintype "input"))
    )
    (net (code "60") (name "DAC_CS") (class "Default")
      (node (ref "U29") (pin "2") (pinfunction "~{CS}_2") (pintype "input"))
    )
    (net (code "61") (name "DAC_SYNC") (class "Default")
      (node (ref "U29") (pin "6") (pinfunction "LAT0/HVC_6") (pintype "passive"))
    )
    (net (code "62") (name "DRAIN_0") (class "Default")
      (node (ref "Q3") (pin "2") (pinfunction "D_2") (pintype "passive"))
    )
    (net (code "63") (name "DRAIN_1") (class "Default")
      (node (ref "Q5") (pin "2") (pinfunction "D_2") (pintype "passive"))
    )
    (net (code "64") (name "DRAIN_2") (class "Default")
      (node (ref "Q6") (pin "2") (pinfunction "D_2") (pintype "passive"))
    )
    (net (code "65") (name "DRAIN_3") (class "Default")
      (node (ref "Q7") (pin "2") (pinfunction "D_2") (pintype "passive"))
    )
    (net (code "66") (name "GND") (class "Default")
      (node (ref "C104") (pin "2") (pinfunction "2_2") (pintype "passive"))
      (node (ref "C105") (pin "2") (pinfunction "2_2") (pintype "passive"))
      (node (ref "C106") (pin "2") (pinfunction "2_2") (pintype "passive"))
      (node (ref "C107") (pin "2") (pinfunction "2_2") (pintype "passive"))
      (node (ref "C108") (pin "2") (pinfunction "2_2") (pintype "passive"))
      (node (ref "C111") (pin "2") (pinfunction "2_2") (pintype "passive"))
      (node (ref "C112") (pin "2") (pinfunction "2_2") (pintype "passive"))
      (node (ref "C113") (pin "2") (pinfunction "2_2") (pintype "passive"))
      (node (ref "C114") (pin "2") (pinfunction "2_2") (pintype "passive"))
      (node (ref "C115") (pin "2") (pinfunction "2_2") (pintype "passive"))
      (node (ref "C116") (pin "2") (pinfunction "2_2") (pintype "passive"))
      (node (ref "C117") (pin "2") (pinfunction "2_2") (pintype "passive"))
      (node (ref "C118") (pin "2") (pinfunction "2_2") (pintype "passive"))
      (node (ref "C121") (pin "2") (pinfunction "2_2") (pintype "passive"))
      (node (ref "C122") (pin "1") (pinfunction "1_1") (pintype "passive"))
      (node (ref "C123") (pin "2") (pinfunction "2_2") (pintype "passive"))
      (node (ref "C124") (pin "2") (pinfunction "2_2") (pintype "passive"))
      (node (ref "C125") (pin "2") (pinfunction "2_2") (pintype "passive"))
      (node (ref "C126") (pin "2") (pinfunction "2_2") (pintype "passive"))
      (node (ref "C127") (pin "2") (pinfunction "2_2") (pintype "passive"))
      (node (ref "C130") (pin "2") (pinfunction "2_2") (pintype "passive"))
      (node (ref "C131") (pin "2") (pinfunction "2_2") (pintype "passive"))
      (node (ref "C132") (pin "2") (pinfunction "2_2") (pintype "passive"))
      (node (ref "C133") (pin "2") (pinfunction "2_2") (pintype "passive"))
      (node (ref "C134") (pin "2") (pinfunction "2_2") (pintype "passive"))
      (node (ref "D10") (pin "1") (pinfunction "A_1") (pintype "passive"))
      (node (ref "D11") (pin "1") (pinfunction "A_1") (pintype "passive"))
      (node (ref "D12") (pin "1") (pinfunction "A_1") (pintype "passive"))
      (node (ref "D13") (pin "1") (pinfunction "A_1") (pintype "passive"))
      (node (ref "D14") (pin "1") (pinfunction "A_1") (pintype "passive"))
      (node (ref "D15") (pin "1") (pinfunction "A_1") (pintype "passive"))
      (node (ref "D8") (pin "1") (pinfunction "A_1") (pintype "passive"))
      (node (ref "D9") (pin "1") (pinfunction "A_1") (pintype "passive"))
      (node (ref "J5") (pin "6") (pinfunction "6_6") (pintype "passive"))
      (node (ref "J7") (pin "6") (pinfunction "6_6") (pintype "passive"))
      (node (ref "J8") (pin "6") (pinfunction "6_6") (pintype "passive"))
      (node (ref "Q3") (pin "3") (pinfunction "S_3") (pintype "passive"))
      (node (ref "Q4") (pin "3") (pinfunction "S_3") (pintype "passive"))
      (node (ref "Q5") (pin "3") (pinfunction "S_3") (pintype "passive"))
      (node (ref "Q6") (pin "3") (pinfunction "S_3") (pintype "passive"))
      (node (ref "Q7") (pin "3") (pinfunction "S_3") (pintype "passive"))
      (node (ref "R100") (pin "2") (pinfunction "2_2") (pintype "passive"))
      (node (ref "R103") (pin "1") (pinfunction "1_1") (pintype "passive"))
      (node (ref "R111") (pin "2") (pinfunction "2_2") (pintype "passive"))
      (node (ref "R112") (pin "1") (pinfunction "1_1") (pintype "passive"))
      (node (ref "R113") (pin "1") (pinfunction "1_1") (pintype "passive"))
      (node (ref "R114") (pin "1") (pinfunction "1_1") (pintype "passive"))
      (node (ref "R117") (pin "1") (pinfunction "1_1") (pintype "passive"))
      (node (ref "R118") (pin "1") (pinfunction "1_1") (pintype "passive"))
      (node (ref "R119") (pin "1") (pinfunction "1_1") (pintype "passive"))
      (node (ref "R123") (pin "1") (pinfunction "1_1") (pintype "passive"))
      (node (ref "R125") (pin "1") (pinfunction "1_1") (pintype "passive"))
      (node (ref "R126") (pin "1") (pinfunction "1_1") (pintype "passive"))
      (node (ref "R128") (pin "1") (pinfunction "1_1") (pintype "passive"))
      (node (ref "R129") (pin "1") (pinfunction "1_1") (pintype "passive"))
      (node (ref "R130") (pin "2") (pinfunction "2_2") (pintype "passive"))
      (node (ref "R135") (pin "1") (pinfunction "1_1") (pintype "passive"))
      (node (ref "R136") (pin "1") (pinfunction "1_1") (pintype "passive"))
      (node (ref "R137") (pin "1") (pinfunction "1_1") (pintype "passive"))
      (node (ref "R142") (pin "1") (pinfunction "1_1") (pintype "passive"))
      (node (ref "R144") (pin "1") (pinfunction "1_1") (pintype "passive"))
      (node (ref "R147") (pin "1") (pinfunction "1_1") (pintype "passive"))
      (node (ref "R149") (pin "1") (pinfunction "1_1") (pintype "passive"))
      (node (ref "R95") (pin "1") (pinfunction "1_1") (pintype "passive"))
      (node (ref "R98") (pin "1") (pinfunction "1_1") (pintype "passive"))
      (node (ref "U25") (pin "11") (pinfunction "V-_11") (pintype "passive"))
      (node (ref "U26") (pin "1") (pinfunction "REFIN-_1") (pintype "input"))
      (node (ref "U26") (pin "17") (pinfunction "DGND_17") (pintype "power_in"))
      (node (ref "U26") (pin "20") (pinfunction "AGND_20") (pintype "power_in"))
      (node (ref "U26") (pin "21") (pinfunction "PAD_21") (pintype "power_in"))
      (node (ref "U27") (pin "10") (pinfunction "GND2_10") (pintype "power_in"))
      (node (ref "U27") (pin "15") (pinfunction "DGND_15") (pintype "power_in"))
      (node (ref "U27") (pin "16") (pinfunction "GND1_16") (pintype "power_in"))
      (node (ref "U27") (pin "21") (pinfunction "EP_21") (pintype "power_in"))
      (node (ref "U28") (pin "11") (pinfunction "V-_11") (pintype "passive"))
      (node (ref "U29") (pin "7") (pinfunction "VSS_7") (pintype "power_in"))
      (node (ref "U30") (pin "10") (pinfunction "GND2_10") (pintype "power_in"))
      (node (ref "U30") (pin "15") (pinfunction "DGND_15") (pintype "power_in"))
      (node (ref "U30") (pin "16") (pinfunction "GND1_16") (pintype "power_in"))
      (node (ref "U30") (pin "21") (pinfunction "EP_21") (pintype "power_in"))
      (node (ref "U31") (pin "11") (pinfunction "V-_11") (pintype "passive"))
      (node (ref "U32") (pin "10") (pinfunction "GND2_10") (pintype "power_in"))
      (node (ref "U32") (pin "15") (pinfunction "DGND_15") (pintype "power_in"))
      (node (ref "U32") (pin "16") (pinfunction "GND1_16") (pintype "power_in"))
      (node (ref "U32") (pin "21") (pinfunction "EP_21") (pintype "power_in"))
      (node (ref "U33") (pin "5") (pinfunction "GND_5") (pintype "power_in"))
      (node (ref "U34") (pin "5") (pinfunction "GND_5") (pintype "power_in"))
    )
    (net (code "67") (name "GPIO_0") (class "Default")
      (node (ref "U33") (pin "1") (pinfunction "I/O_1_1") (pintype "power_in"))
    )
    (net (code "68") (name "GPIO_1") (class "Default")
      (node (ref "U33") (pin "3") (pinfunction "I/O_2_3") (pintype "power_in"))
    )
    (net (code "69") (name "GPIO_2") (class "Default")
      (node (ref "U33") (pin "4") (pinfunction "I/O_3_4") (pintype "power_in"))
    )
    (net (code "70") (name "GPIO_3") (class "Default")
      (node (ref "U33") (pin "6") (pinfunction "I/O_4_6") (pintype "power_in"))
    )
    (net (code "71") (name "GPIO_4") (class "Default")
      (node (ref "U34") (pin "1") (pinfunction "I/O_1_1") (pintype "power_in"))
    )
    (net (code "72") (name "GPIO_5") (class "Default")
      (node (ref "U34") (pin "3") (pinfunction "I/O_2_3") (pintype "power_in"))
    )
    (net (code "73") (name "GPIO_6") (class "Default")
      (node (ref "U34") (pin "4") (pinfunction "I/O_3_4") (pintype "power_in"))
    )
    (net (code "74") (name "GPIO_7") (class "Default")
      (node (ref "U34") (pin "6") (pinfunction "I/O_4_6") (pintype "power_in"))
    )
    (net (code "75") (name "HEATER_PWR") (class "Default")
      (node (ref "LD13") (pin "2") (pinfunction "A_2") (pintype "passive"))
      (node (ref "Q2") (pin "D") (pinfunction "D_D") (pintype "passive"))
    )
    (net (code "76") (name "HEAT_OUT") (class "Default")
      (node (ref "R131") (pin "1") (pinfunction "1_1") (pintype "passive"))
    )
    (net (code "77") (name "Net-(C109-Pad1)") (class "Default")
      (node (ref "C109") (pin "1") (pinfunction "1_1") (pintype "passive"))
      (node (ref "J5") (pin "10") (pinfunction "10_10") (pintype "passive"))
    )
    (net (code "78") (name "Net-(C110-Pad1)") (class "Default")
      (node (ref "C110") (pin "1") (pinfunction "1_1") (pintype "passive"))
      (node (ref "J5") (pin "12") (pinfunction "12_12") (pintype "passive"))
    )
    (net (code "79") (name "Net-(C119-Pad1)") (class "Default")
      (node (ref "C119") (pin "1") (pinfunction "1_1") (pintype "passive"))
      (node (ref "J7") (pin "10") (pinfunction "10_10") (pintype "passive"))
    )
    (net (code "80") (name "Net-(C120-Pad1)") (class "Default")
      (node (ref "C120") (pin "1") (pinfunction "1_1") (pintype "passive"))
      (node (ref "J7") (pin "12") (pinfunction "12_12") (pintype "passive"))
    )
    (net (code "81") (name "Net-(C128-Pad1)") (class "Default")
      (node (ref "C128") (pin "1") (pinfunction "1_1") (pintype "passive"))
      (node (ref "J8") (pin "10") (pinfunction "10_10") (pintype "passive"))
    )
    (net (code "82") (name "Net-(C129-Pad1)") (class "Default")
      (node (ref "C129") (pin "1") (pinfunction "1_1") (pintype "passive"))
      (node (ref "J8") (pin "12") (pinfunction "12_12") (pintype "passive"))
    )
    (net (code "83") (name "Net-(J5-Pad14)") (class "Default")
      (node (ref "J5") (pin "14") (pinfunction "14_14") (pintype "passive"))
      (node (ref "R89") (pin "2") (pinfunction "2_2") (pintype "passive"))
    )
    (net (code "84") (name "Net-(J5-Pad16)") (class "Default")
      (node (ref "J5") (pin "16") (pinfunction "16_16") (pintype "passive"))
      (node (ref "R90") (pin "2") (pinfunction "2_2") (pintype "passive"))
    )
    (net (code "85") (name "Net-(J5-Pad18)") (class "Default")
      (node (ref "J5") (pin "18") (pinfunction "18_18") (pintype "passive"))
      (node (ref "R91") (pin "2") (pinfunction "2_2") (pintype "passive"))
    )
    (net (code "86") (name "Net-(J5-Pad20)") (class "Default")
      (node (ref "J5") (pin "20") (pinfunction "20_20") (pintype "passive"))
      (node (ref "R92") (pin "2") (pinfunction "2_2") (pintype "passive"))
    )
    (net (code "87") (name "Net-(J7-Pad14)") (class "Default")
      (node (ref "J7") (pin "14") (pinfunction "14_14") (pintype "passive"))
      (node (ref "R104") (pin "2") (pinfunction "2_2") (pintype "passive"))
    )
    (net (code "88") (name "Net-(J7-Pad16)") (class "Default")
      (node (ref "J7") (pin "16") (pinfunction "16_16") (pintype "passive"))
      (node (ref "R105") (pin "2") (pinfunction "2_2") (pintype "passive"))
    )
    (net (code "89") (name "Net-(J7-Pad18)") (class "Default")
      (node (ref "J7") (pin "18") (pinfunction "18_18") (pintype "passive"))
      (node (ref "R106") (pin "2") (pinfunction "2_2") (pintype "passive"))
    )
    (net (code "90") (name "Net-(J7-Pad20)") (class "Default")
      (node (ref "J7") (pin "20") (pinfunction "20_20") (pintype "passive"))
      (node (ref "R107") (pin "2") (pinfunction "2_2") (pintype "passive"))
    )
    (net (code "91") (name "Net-(J8-Pad14)") (class "Default")
      (node (ref "J8") (pin "14") (pinfunction "14_14") (pintype "passive"))
      (node (ref "R138") (pin "2") (pinfunction "2_2") (pintype "passive"))
    )
    (net (code "92") (name "Net-(J8-Pad16)") (class "Default")
      (node (ref "J8") (pin "16") (pinfunction "16_16") (pintype "passive"))
      (node (ref "R139") (pin "2") (pinfunction "2_2") (pintype "passive"))
    )
    (net (code "93") (name "Net-(J8-Pad18)") (class "Default")
      (node (ref "J8") (pin "18") (pinfunction "18_18") (pintype "passive"))
      (node (ref "R140") (pin "2") (pinfunction "2_2") (pintype "passive"))
    )
    (net (code "94") (name "Net-(J8-Pad20)") (class "Default")
      (node (ref "J8") (pin "20") (pinfunction "20_20") (pintype "passive"))
      (node (ref "R141") (pin "2") (pinfunction "2_2") (pintype "passive"))
    )
    (net (code "95") (name "Net-(LD13-K)") (class "Default")
      (node (ref "LD13") (pin "1") (pinfunction "K_1") (pintype "passive"))
      (node (ref "R123") (pin "2") (pinfunction "2_2") (pintype "passive"))
    )
    (net (code "96") (name "Net-(Q2-PadG)") (class "Default")
      (node (ref "Q2") (pin "G") (pinfunction "G_G") (pintype "passive"))
      (node (ref "R121") (pin "1") (pinfunction "1_1") (pintype "passive"))
      (node (ref "R122") (pin "2") (pinfunction "2_2") (pintype "passive"))
    )
    (net (code "97") (name "Net-(Q3-G)") (class "Default")
      (node (ref "Q3") (pin "1") (pinfunction "G_1") (pintype "passive"))
      (node (ref "R127") (pin "1") (pinfunction "1_1") (pintype "passive"))
      (node (ref "R128") (pin "2") (pinfunction "2_2") (pintype "passive"))
    )
    (net (code "98") (name "Net-(Q4-D)") (class "Default")
      (node (ref "Q4") (pin "2") (pinfunction "D_2") (pintype "passive"))
      (node (ref "R122") (pin "1") (pinfunction "1_1") (pintype "passive"))
    )
    (net (code "99") (name "Net-(Q4-G)") (class "Default")
      (node (ref "Q4") (pin "1") (pinfunction "G_1") (pintype "passive"))
      (node (ref "R130") (pin "1") (pinfunction "1_1") (pintype "passive"))
      (node (ref "R131") (pin "2") (pinfunction "2_2") (pintype "passive"))
    )
    (net (code "100") (name "Net-(Q5-G)") (class "Default")
      (node (ref "Q5") (pin "1") (pinfunction "G_1") (pintype "passive"))
      (node (ref "R134") (pin "1") (pinfunction "1_1") (pintype "passive"))
      (node (ref "R135") (pin "2") (pinfunction "2_2") (pintype "passive"))
    )
    (net (code "101") (name "Net-(Q6-G)") (class "Default")
      (node (ref "Q6") (pin "1") (pinfunction "G_1") (pintype "passive"))
      (node (ref "R143") (pin "1") (pinfunction "1_1") (pintype "passive"))
      (node (ref "R144") (pin "2") (pinfunction "2_2") (pintype "passive"))
    )
    (net (code "102") (name "Net-(Q7-G)") (class "Default")
      (node (ref "Q7") (pin "1") (pinfunction "G_1") (pintype "passive"))
      (node (ref "R148") (pin "1") (pinfunction "1_1") (pintype "passive"))
      (node (ref "R149") (pin "2") (pinfunction "2_2") (pintype "passive"))
    )
    (net (code "103") (name "Net-(R89-Pad1)") (class "Default")
      (node (ref "R89") (pin "1") (pinfunction "1_1") (pintype "passive"))
      (node (ref "R90") (pin "1") (pinfunction "1_1") (pintype "passive"))
    )
    (net (code "104") (name "Net-(R91-Pad1)") (class "Default")
      (node (ref "R91") (pin "1") (pinfunction "1_1") (pintype "passive"))
      (node (ref "R92") (pin "1") (pinfunction "1_1") (pintype "passive"))
    )
    (net (code "105") (name "Net-(R104-Pad1)") (class "Default")
      (node (ref "R104") (pin "1") (pinfunction "1_1") (pintype "passive"))
      (node (ref "R105") (pin "1") (pinfunction "1_1") (pintype "passive"))
    )
    (net (code "106") (name "Net-(R106-Pad1)") (class "Default")
      (node (ref "R106") (pin "1") (pinfunction "1_1") (pintype "passive"))
      (node (ref "R107") (pin "1") (pinfunction "1_1") (pintype "passive"))
    )
    (net (code "107") (name "Net-(R138-Pad1)") (class "Default")
      (node (ref "R138") (pin "1") (pinfunction "1_1") (pintype "passive"))
      (node (ref "R139") (pin "1") (pinfunction "1_1") (pintype "passive"))
    )
    (net (code "108") (name "Net-(R140-Pad1)") (class "Default")
      (node (ref "R140") (pin "1") (pinfunction "1_1") (pintype "passive"))
      (node (ref "R141") (pin "1") (pinfunction "1_1") (pintype "passive"))
    )
    (net (code "109") (name "Net-(U25A--)") (class "Default")
      (node (ref "R93") (pin "1") (pinfunction "1_1") (pintype "passive"))
      (node (ref "U25") (pin "1") (pinfunction "A_1") (pintype "passive"))
      (node (ref "U25") (pin "2") (pinfunction "-_2") (pintype "passive"))
    )
    (net (code "110") (name "Net-(U25B--)") (class "Default")
      (node (ref "R96") (pin "1") (pinfunction "1_1") (pintype "passive"))
      (node (ref "U25") (pin "6") (pinfunction "-_6") (pintype "passive"))
      (node (ref "U25") (pin "7") (pinfunction "B_7") (pintype "passive"))
    )
    (net (code "111") (name "Net-(U25C--)") (class "Default")
      (node (ref "R101") (pin "1") (pinfunction "1_1") (pintype "passive"))
      (node (ref "U25") (pin "8") (pinfunction "C_8") (pintype "passive"))
      (node (ref "U25") (pin "9") (pinfunction "-_9") (pintype "passive"))
    )
    (net (code "112") (name "Net-(U25D--)") (class "Default")
      (node (ref "R109") (pin "1") (pinfunction "1_1") (pintype "passive"))
      (node (ref "U25") (pin "13") (pinfunction "-_13") (pintype "passive"))
      (node (ref "U25") (pin "14") (pinfunction "D_14") (pintype "passive"))
    )
    (net (code "113") (name "Net-(U28A--)") (class "Default")
      (node (ref "R115") (pin "1") (pinfunction "1_1") (pintype "passive"))
      (node (ref "U28") (pin "1") (pinfunction "A_1") (pintype "passive"))
      (node (ref "U28") (pin "2") (pinfunction "-_2") (pintype "passive"))
    )
    (net (code "114") (name "Net-(U28B--)") (class "Default")
      (node (ref "R120") (pin "1") (pinfunction "1_1") (pintype "passive"))
      (node (ref "U28") (pin "6") (pinfunction "-_6") (pintype "passive"))
      (node (ref "U28") (pin "7") (pinfunction "B_7") (pintype "passive"))
    )
    (net (code "115") (name "Net-(U28C--)") (class "Default")
      (node (ref "R132") (pin "1") (pinfunction "1_1") (pintype "passive"))
      (node (ref "U28") (pin "8") (pinfunction "C_8") (pintype "passive"))
      (node (ref "U28") (pin "9") (pinfunction "-_9") (pintype "passive"))
    )
    (net (code "116") (name "Net-(U28D--)") (class "Default")
      (node (ref "R145") (pin "1") (pinfunction "1_1") (pintype "passive"))
      (node (ref "U28") (pin "13") (pinfunction "-_13") (pintype "passive"))
      (node (ref "U28") (pin "14") (pinfunction "D_14") (pintype "passive"))
    )
    (net (code "117") (name "Net-(U29-VOUT0)") (class "Default")
      (node (ref "U29") (pin "4") (pinfunction "VOUT0_4") (pintype "passive"))
      (node (ref "U31") (pin "3") (pinfunction "+_3") (pintype "passive"))
    )
    (net (code "118") (name "Net-(U29-VOUT1)") (class "Default")
      (node (ref "U29") (pin "5") (pinfunction "VOUT1_5") (pintype "passive"))
      (node (ref "U31") (pin "10") (pinfunction "+_10") (pintype "passive"))
    )
    (net (code "119") (name "Net-(U31A--)") (class "Default")
      (node (ref "R100") (pin "1") (pinfunction "1_1") (pintype "passive"))
      (node (ref "R99") (pin "1") (pinfunction "1_1") (pintype "passive"))
      (node (ref "U31") (pin "2") (pinfunction "-_2") (pintype "passive"))
    )
    (net (code "120") (name "Net-(U31A-A)") (class "Default")
      (node (ref "R99") (pin "2") (pinfunction "2_2") (pintype "passive"))
      (node (ref "U31") (pin "1") (pinfunction "A_1") (pintype "passive"))
      (node (ref "U31") (pin "5") (pinfunction "+_5") (pintype "passive"))
    )
    (net (code "121") (name "Net-(U31C--)") (class "Default")
      (node (ref "R108") (pin "1") (pinfunction "1_1") (pintype "passive"))
      (node (ref "R111") (pin "1") (pinfunction "1_1") (pintype "passive"))
      (node (ref "U31") (pin "9") (pinfunction "-_9") (pintype "passive"))
    )
    (net (code "122") (name "Net-(U31C-C)") (class "Default")
      (node (ref "R108") (pin "2") (pinfunction "2_2") (pintype "passive"))
      (node (ref "U31") (pin "12") (pinfunction "+_12") (pintype "passive"))
      (node (ref "U31") (pin "8") (pinfunction "C_8") (pintype "passive"))
    )
    (net (code "123") (name "OUT_0") (class "Default")
      (node (ref "R127") (pin "2") (pinfunction "2_2") (pintype "passive"))
    )
    (net (code "124") (name "OUT_1") (class "Default")
      (node (ref "R134") (pin "2") (pinfunction "2_2") (pintype "passive"))
    )
    (net (code "125") (name "OUT_2") (class "Default")
      (node (ref "R143") (pin "2") (pinfunction "2_2") (pintype "passive"))
    )
    (net (code "126") (name "OUT_3") (class "Default")
      (node (ref "R148") (pin "2") (pinfunction "2_2") (pintype "passive"))
    )
    (net (code "127") (name "PT100_CS_1") (class "Default")
      (node (ref "U27") (pin "13") (pinfunction "~{CS}_13") (pintype "input"))
    )
    (net (code "128") (name "PT100_CS_2") (class "Default")
      (node (ref "U30") (pin "13") (pinfunction "~{CS}_13") (pintype "input"))
    )
    (net (code "129") (name "PT100_CS_3") (class "Default")
      (node (ref "U32") (pin "13") (pinfunction "~{CS}_13") (pintype "input"))
    )
    (net (code "130") (name "PT100_IRQ_1") (class "Default")
      (node (ref "U27") (pin "18") (pinfunction "~{DRDY}_18") (pintype "output"))
    )
    (net (code "131") (name "PT100_IRQ_2") (class "Default")
      (node (ref "U30") (pin "18") (pinfunction "~{DRDY}_18") (pintype "output"))
    )
    (net (code "132") (name "PT100_IRQ_3") (class "Default")
      (node (ref "U32") (pin "18") (pinfunction "~{DRDY}_18") (pintype "output"))
    )
    (net (code "133") (name "S+_P1") (class "Default")
      (node (ref "J5") (pin "11") (pinfunction "11_11") (pintype "passive"))
      (node (ref "J5") (pin "2") (pinfunction "2_2") (pintype "passive"))
      (node (ref "J5") (pin "9") (pinfunction "9_9") (pintype "passive"))
      (node (ref "U27") (pin "7") (pinfunction "RTDIN+_7") (pintype "input"))
    )
    (net (code "134") (name "S+_P2") (class "Default")
      (node (ref "J7") (pin "11") (pinfunction "11_11") (pintype "passive"))
      (node (ref "J7") (pin "2") (pinfunction "2_2") (pintype "passive"))
      (node (ref "J7") (pin "9") (pinfunction "9_9") (pintype "passive"))
      (node (ref "U30") (pin "7") (pinfunction "RTDIN+_7") (pintype "input"))
    )
    (net (code "135") (name "S+_P3") (class "Default")
      (node (ref "J8") (pin "11") (pinfunction "11_11") (pintype "passive"))
      (node (ref "J8") (pin "2") (pinfunction "2_2") (pintype "passive"))
      (node (ref "J8") (pin "9") (pinfunction "9_9") (pintype "passive"))
      (node (ref "U32") (pin "7") (pinfunction "RTDIN+_7") (pintype "input"))
    )
    (net (code "136") (name "S-_P1") (class "Default")
      (node (ref "C109") (pin "2") (pinfunction "2_2") (pintype "passive"))
      (node (ref "C110") (pin "2") (pinfunction "2_2") (pintype "passive"))
      (node (ref "J5") (pin "3") (pinfunction "3_3") (pintype "passive"))
      (node (ref "U27") (pin "8") (pinfunction "RTDIN-_8") (pintype "input"))
    )
    (net (code "137") (name "S-_P2") (class "Default")
      (node (ref "C119") (pin "2") (pinfunction "2_2") (pintype "passive"))
      (node (ref "C120") (pin "2") (pinfunction "2_2") (pintype "passive"))
      (node (ref "J7") (pin "3") (pinfunction "3_3") (pintype "passive"))
      (node (ref "U30") (pin "8") (pinfunction "RTDIN-_8") (pintype "input"))
    )
    (net (code "138") (name "S-_P3") (class "Default")
      (node (ref "C128") (pin "2") (pinfunction "2_2") (pintype "passive"))
      (node (ref "C129") (pin "2") (pinfunction "2_2") (pintype "passive"))
      (node (ref "J8") (pin "3") (pinfunction "3_3") (pintype "passive"))
      (node (ref "U32") (pin "8") (pinfunction "RTDIN-_8") (pintype "input"))
    )
    (net (code "139") (name "unconnected-(U26-MCLK-Pad16)") (class "Default")
      (node (ref "U26") (pin "16") (pinfunction "MCLK_16") (pintype "bidirectional"))
    )
    (net (code "140") (name "unconnected-(U27-NC-Pad17)") (class "Default")
      (node (ref "U27") (pin "17") (pinfunction "NC_17") (pintype "passive"))
    )
    (net (code "141") (name "unconnected-(U30-NC-Pad17)") (class "Default")
      (node (ref "U30") (pin "17") (pinfunction "NC_17") (pintype "passive"))
    )
    (net (code "142") (name "unconnected-(U32-NC-Pad17)") (class "Default")
      (node (ref "U32") (pin "17") (pinfunction "NC_17") (pintype "passive"))
    )
  )
)
